# Sens_LM75.net
KiCad netlist of a schematic drawn in EAGLE
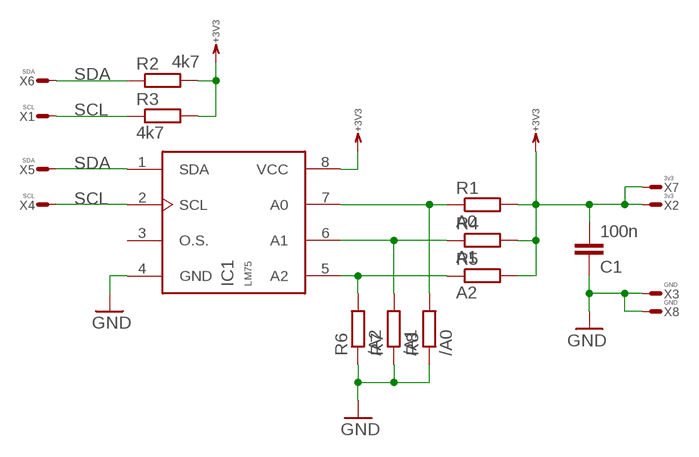
[diagram p0: schematic, sheet 1]

(export (version "E")
  (design (tool "Eeschema 10.0.6"))
  (components
    (comp (ref "C1")
      (value "100n")
      (footprint "eagle-import:0603")
      (libsource (lib "eagle-import") (part "C0603"))
    )
    (comp (ref "IC1")
      (value "LM75")
      (footprint "eagle-import:SO8")
      (libsource (lib "eagle-import") (part "LM75M"))
    )
    (comp (ref "R1")
      (value "A0")
      (footprint "eagle-import:0603")
      (libsource (lib "eagle-import") (part "R0603"))
    )
    (comp (ref "R2")
      (value "4k7")
      (footprint "eagle-import:0603")
      (libsource (lib "eagle-import") (part "R0603"))
    )
    (comp (ref "R3")
      (value "4k7")
      (footprint "eagle-import:0603")
      (libsource (lib "eagle-import") (part "R0603"))
    )
    (comp (ref "R4")
      (value "A1")
      (footprint "eagle-import:0603")
      (libsource (lib "eagle-import") (part "R0603"))
    )
    (comp (ref "R5")
      (value "A2")
      (footprint "eagle-import:0603")
      (libsource (lib "eagle-import") (part "R0603"))
    )
    (comp (ref "R6")
      (value "/A2")
      (footprint "eagle-import:0603")
      (libsource (lib "eagle-import") (part "R0603"))
    )
    (comp (ref "R7")
      (value "/A1")
      (footprint "eagle-import:0603")
      (libsource (lib "eagle-import") (part "R0603"))
    )
    (comp (ref "R8")
      (value "/A0")
      (footprint "eagle-import:0603")
      (libsource (lib "eagle-import") (part "R0603"))
    )
    (comp (ref "X1")
      (value "SCL")
      (footprint "eagle-import:T1.6_0.9")
      (libsource (lib "eagle-import") (part "WIREPADT1.6/0.9"))
    )
    (comp (ref "X2")
      (value "3v3")
      (footprint "eagle-import:T1.6_0.9")
      (libsource (lib "eagle-import") (part "WIREPADT1.6/0.9"))
    )
    (comp (ref "X3")
      (value "GND")
      (footprint "eagle-import:T1.6_0.9")
      (libsource (lib "eagle-import") (part "WIREPADT1.6/0.9"))
    )
    (comp (ref "X4")
      (value "SCL")
      (footprint "eagle-import:T1.6_0.9")
      (libsource (lib "eagle-import") (part "WIREPADT1.6/0.9"))
    )
    (comp (ref "X5")
      (value "SDA")
      (footprint "eagle-import:T1.6_0.9")
      (libsource (lib "eagle-import") (part "WIREPADT1.6/0.9"))
    )
    (comp (ref "X6")
      (value "SDA")
      (footprint "eagle-import:T1.6_0.9")
      (libsource (lib "eagle-import") (part "WIREPADT1.6/0.9"))
    )
    (comp (ref "X7")
      (value "3v3")
      (footprint "eagle-import:T1.6_0.9")
      (libsource (lib "eagle-import") (part "WIREPADT1.6/0.9"))
    )
    (comp (ref "X8")
      (value "GND")
      (footprint "eagle-import:T1.6_0.9")
      (libsource (lib "eagle-import") (part "WIREPADT1.6/0.9"))
    )
  )
  (nets
    (net (code "1") (name "+3V3") (class "Default")
      (node (ref "C1") (pin "2") (pinfunction "2_2") (pintype "passive"))
      (node (ref "IC1") (pin "8") (pinfunction "VCC_8") (pintype "bidirectional"))
      (node (ref "R1") (pin "2") (pinfunction "2_2") (pintype "passive"))
      (node (ref "R2") (pin "2") (pinfunction "2_2") (pintype "passive"))
      (node (ref "R3") (pin "2") (pinfunction "2_2") (pintype "passive"))
      (node (ref "R4") (pin "2") (pinfunction "2_2") (pintype "passive"))
      (node (ref "R5") (pin "2") (pinfunction "2_2") (pintype "passive"))
      (node (ref "X2") (pin "1") (pinfunction "S_1") (pintype "passive"))
      (node (ref "X7") (pin "1") (pinfunction "S_1") (pintype "passive"))
    )
    (net (code "2") (name "/SCL") (class "Default")
      (node (ref "IC1") (pin "2") (pinfunction "SCL_2") (pintype "bidirectional"))
      (node (ref "R3") (pin "1") (pinfunction "1_1") (pintype "passive"))
      (node (ref "X1") (pin "1") (pinfunction "S_1") (pintype "passive"))
      (node (ref "X4") (pin "1") (pinfunction "S_1") (pintype "passive"))
    )
    (net (code "3") (name "/SDA") (class "Default")
      (node (ref "IC1") (pin "1") (pinfunction "SDA_1") (pintype "bidirectional"))
      (node (ref "R2") (pin "1") (pinfunction "1_1") (pintype "passive"))
      (node (ref "X5") (pin "1") (pinfunction "S_1") (pintype "passive"))
      (node (ref "X6") (pin "1") (pinfunction "S_1") (pintype "passive"))
    )
    (net (code "4") (name "GND") (class "Default")
      (node (ref "C1") (pin "1") (pinfunction "1_1") (pintype "passive"))
      (node (ref "IC1") (pin "4") (pinfunction "GND_4") (pintype "bidirectional"))
      (node (ref "R6") (pin "1") (pinfunction "1_1") (pintype "passive"))
      (node (ref "R7") (pin "1") (pinfunction "1_1") (pintype "passive"))
      (node (ref "R8") (pin "1") (pinfunction "1_1") (pintype "passive"))
      (node (ref "X3") (pin "1") (pinfunction "S_1") (pintype "passive"))
      (node (ref "X8") (pin "1") (pinfunction "S_1") (pintype "passive"))
    )
    (net (code "5") (name "Net-(IC1-A0)") (class "Default")
      (node (ref "IC1") (pin "7") (pinfunction "A0_7") (pintype "input"))
      (node (ref "R1") (pin "1") (pinfunction "1_1") (pintype "passive"))
      (node (ref "R8") (pin "2") (pinfunction "2_2") (pintype "passive"))
    )
    (net (code "6") (name "Net-(IC1-A1)") (class "Default")
      (node (ref "IC1") (pin "6") (pinfunction "A1_6") (pintype "input"))
      (node (ref "R4") (pin "1") (pinfunction "1_1") (pintype "passive"))
      (node (ref "R7") (pin "2") (pinfunction "2_2") (pintype "passive"))
    )
    (net (code "7") (name "Net-(IC1-A2)") (class "Default")
      (node (ref "IC1") (pin "5") (pinfunction "A2_5") (pintype "input"))
      (node (ref "R5") (pin "1") (pinfunction "1_1") (pintype "passive"))
      (node (ref "R6") (pin "2") (pinfunction "2_2") (pintype "passive"))
    )
    (net (code "8") (name "unconnected-(IC1-O.S.-Pad3)") (class "Default")
      (node (ref "IC1") (pin "3") (pinfunction "O.S._3") (pintype "open_collector"))
    )
  )
)
